# stm32g071_pcb.net
KiCad netlist of a schematic drawn in EAGLE
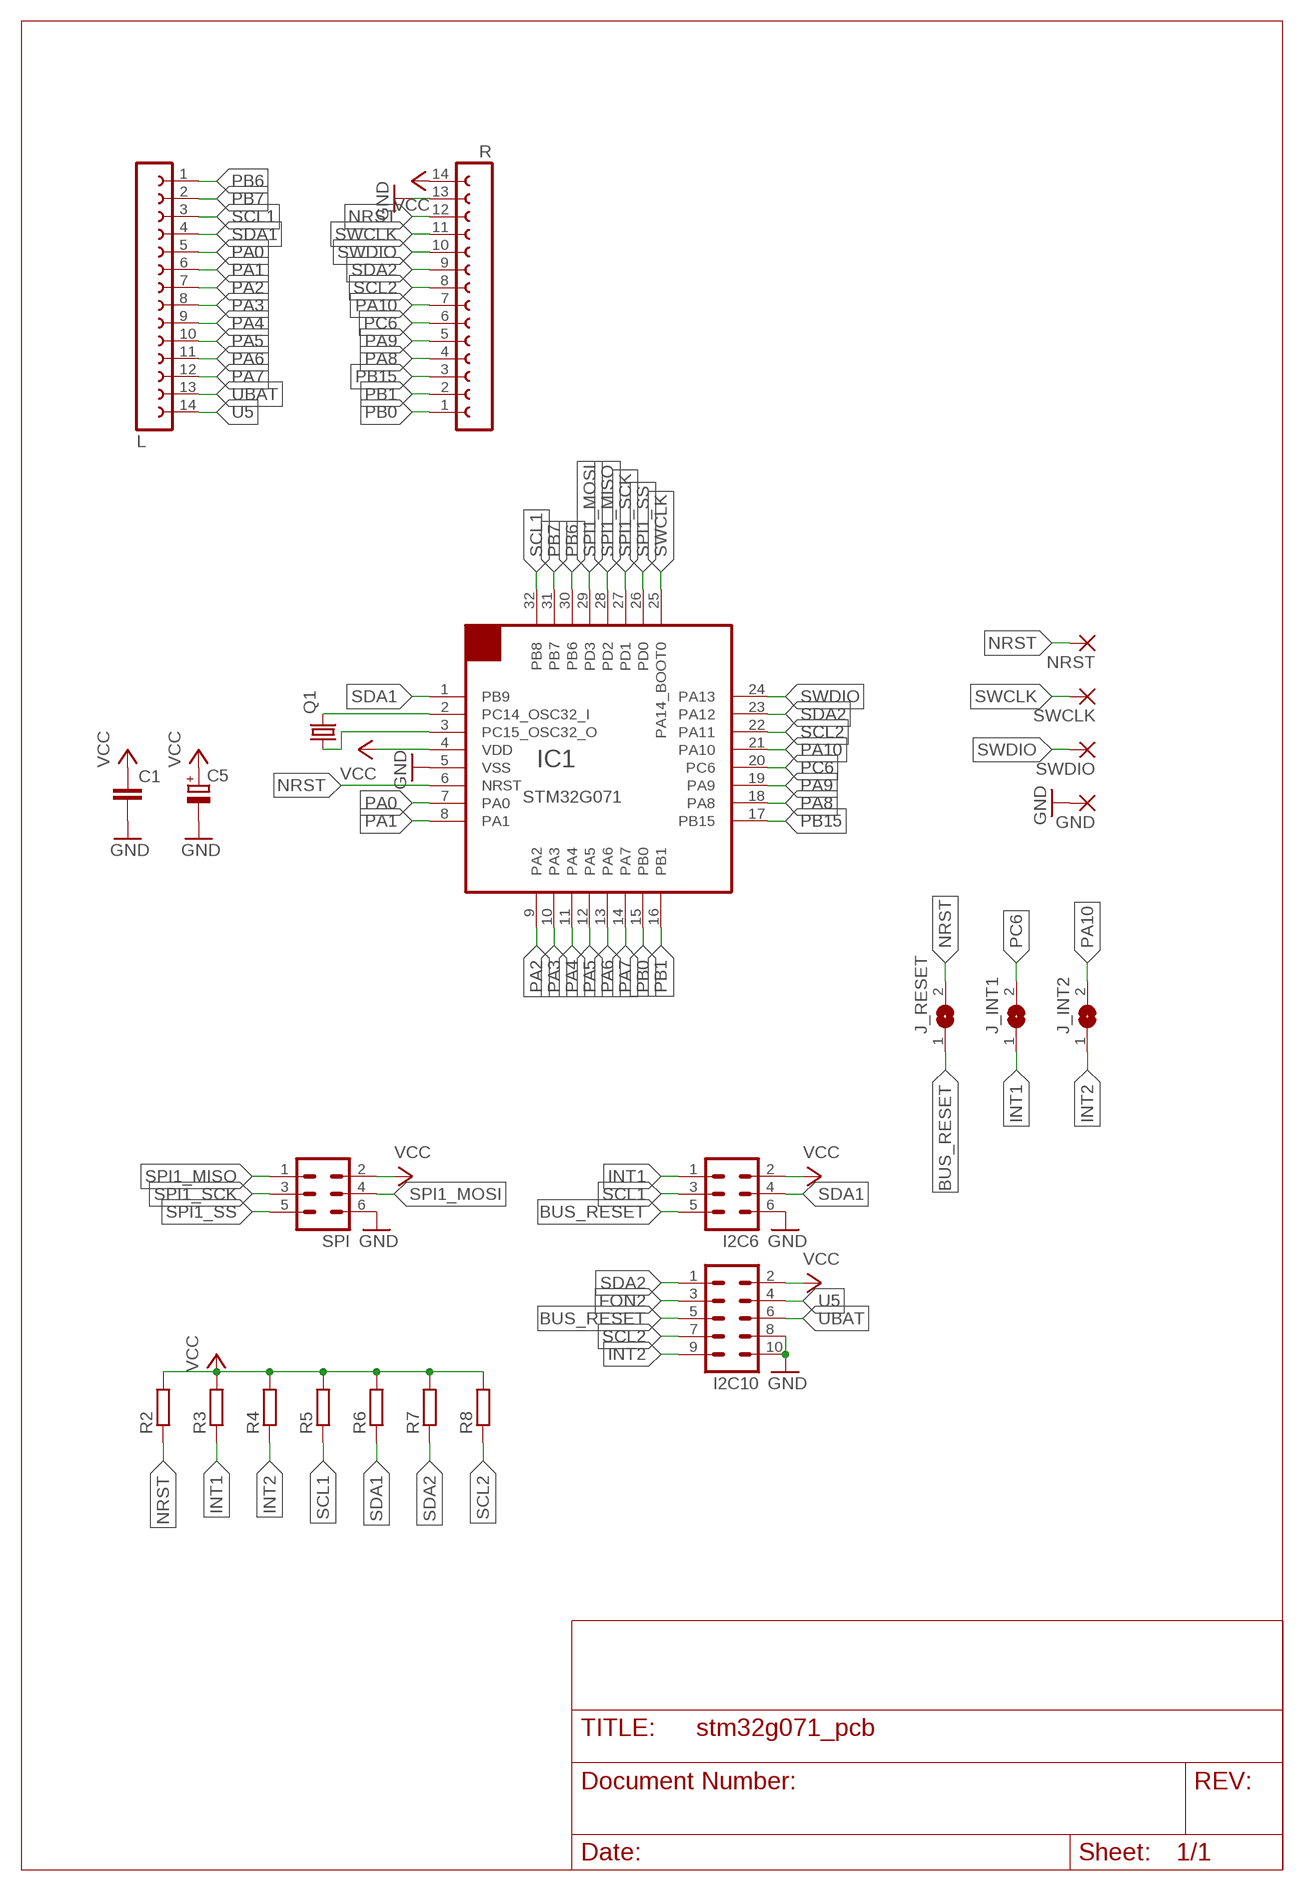
[diagram p0: schematic, sheet 1]

(export (version "E")
  (design (tool "Eeschema 10.0.6"))
  (components
    (comp (ref "C1")
      (value "C-EUC0805")
      (footprint "eagle-import:C0805")
      (libsource (lib "eagle-import") (part "C-EUC0805"))
    )
    (comp (ref "C5")
      (value "CPOL-EUB/3528-21W")
      (footprint "eagle-import:B_3528-21W")
      (libsource (lib "eagle-import") (part "CPOL-EUB/3528-21W"))
    )
    (comp (ref "GND")
      (value "1,6/0,8")
      (footprint "eagle-import:1,6_0,8")
      (libsource (lib "eagle-import") (part "1,6/0,8"))
    )
    (comp (ref "I2C6")
      (value "ML6")
      (footprint "eagle-import:ML6")
      (libsource (lib "eagle-import") (part "ML6"))
    )
    (comp (ref "I2C10")
      (value "ML10")
      (footprint "eagle-import:ML10")
      (libsource (lib "eagle-import") (part "ML10"))
    )
    (comp (ref "IC1")
      (value "STM32G071")
      (footprint "eagle-import:LQFP-32")
      (libsource (lib "eagle-import") (part "STM32G071KBT6N"))
    )
    (comp (ref "J_INT1")
      (value "SJ")
      (footprint "eagle-import:SJ")
      (libsource (lib "eagle-import") (part "SJ"))
    )
    (comp (ref "J_INT2")
      (value "SJ")
      (footprint "eagle-import:SJ")
      (libsource (lib "eagle-import") (part "SJ"))
    )
    (comp (ref "J_RESET")
      (value "SJ")
      (footprint "eagle-import:SJ")
      (libsource (lib "eagle-import") (part "SJ"))
    )
    (comp (ref "L")
      (value "FE14-1")
      (footprint "eagle-import:FE14")
      (libsource (lib "eagle-import") (part "FE14-1"))
    )
    (comp (ref "NRST")
      (value "1,6/0,8")
      (footprint "eagle-import:1,6_0,8")
      (libsource (lib "eagle-import") (part "1,6/0,8"))
    )
    (comp (ref "Q1")
      (value "CRYSTALTC26V")
      (footprint "eagle-import:TC26V")
      (libsource (lib "eagle-import") (part "CRYSTALTC26V"))
    )
    (comp (ref "R")
      (value "FE14-1")
      (footprint "eagle-import:FE14")
      (libsource (lib "eagle-import") (part "FE14-1"))
    )
    (comp (ref "R2")
      (value "R-EU_R0805")
      (footprint "eagle-import:R0805")
      (libsource (lib "eagle-import") (part "R-EU_R0805"))
    )
    (comp (ref "R3")
      (value "R-EU_R0805")
      (footprint "eagle-import:R0805")
      (libsource (lib "eagle-import") (part "R-EU_R0805"))
    )
    (comp (ref "R4")
      (value "R-EU_R0805")
      (footprint "eagle-import:R0805")
      (libsource (lib "eagle-import") (part "R-EU_R0805"))
    )
    (comp (ref "R5")
      (value "R-EU_R0805")
      (footprint "eagle-import:R0805")
      (libsource (lib "eagle-import") (part "R-EU_R0805"))
    )
    (comp (ref "R6")
      (value "R-EU_R0805")
      (footprint "eagle-import:R0805")
      (libsource (lib "eagle-import") (part "R-EU_R0805"))
    )
    (comp (ref "R7")
      (value "R-EU_R0805")
      (footprint "eagle-import:R0805")
      (libsource (lib "eagle-import") (part "R-EU_R0805"))
    )
    (comp (ref "R8")
      (value "R-EU_R0805")
      (footprint "eagle-import:R0805")
      (libsource (lib "eagle-import") (part "R-EU_R0805"))
    )
    (comp (ref "SPI")
      (value "ML6")
      (footprint "eagle-import:ML6")
      (libsource (lib "eagle-import") (part "ML6"))
    )
    (comp (ref "SWCLK")
      (value "1,6/0,8")
      (footprint "eagle-import:1,6_0,8")
      (libsource (lib "eagle-import") (part "1,6/0,8"))
    )
    (comp (ref "SWDIO")
      (value "1,6/0,8")
      (footprint "eagle-import:1,6_0,8")
      (libsource (lib "eagle-import") (part "1,6/0,8"))
    )
  )
  (nets
    (net (code "1") (name "BUS_RESET") (class "Default")
      (node (ref "I2C10") (pin "5") (pinfunction "5_5") (pintype "passive"))
      (node (ref "I2C6") (pin "5") (pinfunction "5_5") (pintype "passive"))
      (node (ref "J_RESET") (pin "1") (pinfunction "1_1") (pintype "passive"))
    )
    (net (code "2") (name "FON2") (class "Default")
      (node (ref "I2C10") (pin "3") (pinfunction "3_3") (pintype "passive"))
    )
    (net (code "3") (name "GND") (class "Default")
      (node (ref "C1") (pin "2") (pinfunction "2_2") (pintype "passive"))
      (node (ref "C5") (pin "-") (pinfunction "-_-") (pintype "passive"))
      (node (ref "GND") (pin "1") (pinfunction "P_1") (pintype "passive"))
      (node (ref "I2C10") (pin "10") (pinfunction "10_10") (pintype "passive"))
      (node (ref "I2C10") (pin "8") (pinfunction "8_8") (pintype "passive"))
      (node (ref "I2C6") (pin "6") (pinfunction "6_6") (pintype "passive"))
      (node (ref "IC1") (pin "5") (pinfunction "VSS_5") (pintype "power_in"))
      (node (ref "R") (pin "13") (pinfunction "13_13") (pintype "passive"))
      (node (ref "SPI") (pin "6") (pinfunction "6_6") (pintype "passive"))
    )
    (net (code "4") (name "INT1") (class "Default")
      (node (ref "I2C6") (pin "1") (pinfunction "1_1") (pintype "passive"))
      (node (ref "J_INT1") (pin "1") (pinfunction "1_1") (pintype "passive"))
      (node (ref "R3") (pin "1") (pinfunction "1_1") (pintype "passive"))
    )
    (net (code "5") (name "INT2") (class "Default")
      (node (ref "I2C10") (pin "9") (pinfunction "9_9") (pintype "passive"))
      (node (ref "J_INT2") (pin "1") (pinfunction "1_1") (pintype "passive"))
      (node (ref "R4") (pin "1") (pinfunction "1_1") (pintype "passive"))
    )
    (net (code "6") (name "NRST") (class "Default")
      (node (ref "IC1") (pin "6") (pinfunction "NRST_6") (pintype "bidirectional"))
      (node (ref "J_RESET") (pin "2") (pinfunction "2_2") (pintype "passive"))
      (node (ref "NRST") (pin "1") (pinfunction "P_1") (pintype "passive"))
      (node (ref "R") (pin "12") (pinfunction "12_12") (pintype "passive"))
      (node (ref "R2") (pin "1") (pinfunction "1_1") (pintype "passive"))
    )
    (net (code "7") (name "Net-(IC1-PC14_OSC32_I)") (class "Default")
      (node (ref "IC1") (pin "2") (pinfunction "PC14_OSC32_I_2") (pintype "bidirectional"))
      (node (ref "Q1") (pin "2") (pinfunction "2_2") (pintype "passive"))
    )
    (net (code "8") (name "Net-(IC1-PC15_OSC32_O)") (class "Default")
      (node (ref "IC1") (pin "3") (pinfunction "PC15_OSC32_O_3") (pintype "bidirectional"))
      (node (ref "Q1") (pin "1") (pinfunction "1_1") (pintype "passive"))
    )
    (net (code "9") (name "PA0") (class "Default")
      (node (ref "IC1") (pin "7") (pinfunction "PA0_7") (pintype "bidirectional"))
      (node (ref "L") (pin "5") (pinfunction "5_5") (pintype "passive"))
    )
    (net (code "10") (name "PA1") (class "Default")
      (node (ref "IC1") (pin "8") (pinfunction "PA1_8") (pintype "bidirectional"))
      (node (ref "L") (pin "6") (pinfunction "6_6") (pintype "passive"))
    )
    (net (code "11") (name "PA2") (class "Default")
      (node (ref "IC1") (pin "9") (pinfunction "PA2_9") (pintype "bidirectional"))
      (node (ref "L") (pin "7") (pinfunction "7_7") (pintype "passive"))
    )
    (net (code "12") (name "PA3") (class "Default")
      (node (ref "IC1") (pin "10") (pinfunction "PA3_10") (pintype "bidirectional"))
      (node (ref "L") (pin "8") (pinfunction "8_8") (pintype "passive"))
    )
    (net (code "13") (name "PA4") (class "Default")
      (node (ref "IC1") (pin "11") (pinfunction "PA4_11") (pintype "bidirectional"))
      (node (ref "L") (pin "9") (pinfunction "9_9") (pintype "passive"))
    )
    (net (code "14") (name "PA5") (class "Default")
      (node (ref "IC1") (pin "12") (pinfunction "PA5_12") (pintype "bidirectional"))
      (node (ref "L") (pin "10") (pinfunction "10_10") (pintype "passive"))
    )
    (net (code "15") (name "PA6") (class "Default")
      (node (ref "IC1") (pin "13") (pinfunction "PA6_13") (pintype "bidirectional"))
      (node (ref "L") (pin "11") (pinfunction "11_11") (pintype "passive"))
    )
    (net (code "16") (name "PA7") (class "Default")
      (node (ref "IC1") (pin "14") (pinfunction "PA7_14") (pintype "bidirectional"))
      (node (ref "L") (pin "12") (pinfunction "12_12") (pintype "passive"))
    )
    (net (code "17") (name "PA8") (class "Default")
      (node (ref "IC1") (pin "18") (pinfunction "PA8_18") (pintype "bidirectional"))
      (node (ref "R") (pin "4") (pinfunction "4_4") (pintype "passive"))
    )
    (net (code "18") (name "PA9") (class "Default")
      (node (ref "IC1") (pin "19") (pinfunction "PA9_19") (pintype "bidirectional"))
      (node (ref "R") (pin "5") (pinfunction "5_5") (pintype "passive"))
    )
    (net (code "19") (name "PA10") (class "Default")
      (node (ref "IC1") (pin "21") (pinfunction "PA10_21") (pintype "bidirectional"))
      (node (ref "J_INT2") (pin "2") (pinfunction "2_2") (pintype "passive"))
      (node (ref "R") (pin "7") (pinfunction "7_7") (pintype "passive"))
    )
    (net (code "20") (name "PB0") (class "Default")
      (node (ref "IC1") (pin "15") (pinfunction "PB0_15") (pintype "bidirectional"))
      (node (ref "R") (pin "1") (pinfunction "1_1") (pintype "passive"))
    )
    (net (code "21") (name "PB1") (class "Default")
      (node (ref "IC1") (pin "16") (pinfunction "PB1_16") (pintype "bidirectional"))
      (node (ref "R") (pin "2") (pinfunction "2_2") (pintype "passive"))
    )
    (net (code "22") (name "PB6") (class "Default")
      (node (ref "IC1") (pin "30") (pinfunction "PB6_30") (pintype "bidirectional"))
      (node (ref "L") (pin "1") (pinfunction "1_1") (pintype "passive"))
    )
    (net (code "23") (name "PB7") (class "Default")
      (node (ref "IC1") (pin "31") (pinfunction "PB7_31") (pintype "bidirectional"))
      (node (ref "L") (pin "2") (pinfunction "2_2") (pintype "passive"))
    )
    (net (code "24") (name "PB15") (class "Default")
      (node (ref "IC1") (pin "17") (pinfunction "PB15_17") (pintype "bidirectional"))
      (node (ref "R") (pin "3") (pinfunction "3_3") (pintype "passive"))
    )
    (net (code "25") (name "PC6") (class "Default")
      (node (ref "IC1") (pin "20") (pinfunction "PC6_20") (pintype "bidirectional"))
      (node (ref "J_INT1") (pin "2") (pinfunction "2_2") (pintype "passive"))
      (node (ref "R") (pin "6") (pinfunction "6_6") (pintype "passive"))
    )
    (net (code "26") (name "SCL1") (class "Default")
      (node (ref "I2C6") (pin "3") (pinfunction "3_3") (pintype "passive"))
      (node (ref "IC1") (pin "32") (pinfunction "PB8_32") (pintype "bidirectional"))
      (node (ref "L") (pin "3") (pinfunction "3_3") (pintype "passive"))
      (node (ref "R5") (pin "1") (pinfunction "1_1") (pintype "passive"))
    )
    (net (code "27") (name "SCL2") (class "Default")
      (node (ref "I2C10") (pin "7") (pinfunction "7_7") (pintype "passive"))
      (node (ref "IC1") (pin "22") (pinfunction "PA11_22") (pintype "bidirectional"))
      (node (ref "R") (pin "8") (pinfunction "8_8") (pintype "passive"))
      (node (ref "R8") (pin "1") (pinfunction "1_1") (pintype "passive"))
    )
    (net (code "28") (name "SDA1") (class "Default")
      (node (ref "I2C6") (pin "4") (pinfunction "4_4") (pintype "passive"))
      (node (ref "IC1") (pin "1") (pinfunction "PB9_1") (pintype "bidirectional"))
      (node (ref "L") (pin "4") (pinfunction "4_4") (pintype "passive"))
      (node (ref "R6") (pin "1") (pinfunction "1_1") (pintype "passive"))
    )
    (net (code "29") (name "SDA2") (class "Default")
      (node (ref "I2C10") (pin "1") (pinfunction "1_1") (pintype "passive"))
      (node (ref "IC1") (pin "23") (pinfunction "PA12_23") (pintype "bidirectional"))
      (node (ref "R") (pin "9") (pinfunction "9_9") (pintype "passive"))
      (node (ref "R7") (pin "1") (pinfunction "1_1") (pintype "passive"))
    )
    (net (code "30") (name "SPI1_MISO") (class "Default")
      (node (ref "IC1") (pin "28") (pinfunction "PD2_28") (pintype "bidirectional"))
      (node (ref "SPI") (pin "1") (pinfunction "1_1") (pintype "passive"))
    )
    (net (code "31") (name "SPI1_MOSI") (class "Default")
      (node (ref "IC1") (pin "29") (pinfunction "PD3_29") (pintype "bidirectional"))
      (node (ref "SPI") (pin "4") (pinfunction "4_4") (pintype "passive"))
    )
    (net (code "32") (name "SPI1_SCK") (class "Default")
      (node (ref "IC1") (pin "27") (pinfunction "PD1_27") (pintype "bidirectional"))
      (node (ref "SPI") (pin "3") (pinfunction "3_3") (pintype "passive"))
    )
    (net (code "33") (name "SPI1_SS") (class "Default")
      (node (ref "IC1") (pin "26") (pinfunction "PD0_26") (pintype "bidirectional"))
      (node (ref "SPI") (pin "5") (pinfunction "5_5") (pintype "passive"))
    )
    (net (code "34") (name "SWCLK") (class "Default")
      (node (ref "IC1") (pin "25") (pinfunction "PA14_BOOT0_25") (pintype "bidirectional"))
      (node (ref "R") (pin "11") (pinfunction "11_11") (pintype "passive"))
      (node (ref "SWCLK") (pin "1") (pinfunction "P_1") (pintype "passive"))
    )
    (net (code "35") (name "SWDIO") (class "Default")
      (node (ref "IC1") (pin "24") (pinfunction "PA13_24") (pintype "bidirectional"))
      (node (ref "R") (pin "10") (pinfunction "10_10") (pintype "passive"))
      (node (ref "SWDIO") (pin "1") (pinfunction "P_1") (pintype "passive"))
    )
    (net (code "36") (name "U5") (class "Default")
      (node (ref "I2C10") (pin "4") (pinfunction "4_4") (pintype "passive"))
      (node (ref "L") (pin "14") (pinfunction "14_14") (pintype "passive"))
    )
    (net (code "37") (name "UBAT") (class "Default")
      (node (ref "I2C10") (pin "6") (pinfunction "6_6") (pintype "passive"))
      (node (ref "L") (pin "13") (pinfunction "13_13") (pintype "passive"))
    )
    (net (code "38") (name "VCC") (class "Default")
      (node (ref "C1") (pin "1") (pinfunction "1_1") (pintype "passive"))
      (node (ref "C5") (pin "+") (pinfunction "+_+") (pintype "passive"))
      (node (ref "I2C10") (pin "2") (pinfunction "2_2") (pintype "passive"))
      (node (ref "I2C6") (pin "2") (pinfunction "2_2") (pintype "passive"))
      (node (ref "IC1") (pin "4") (pinfunction "VDD_4") (pintype "power_in"))
      (node (ref "R") (pin "14") (pinfunction "14_14") (pintype "passive"))
      (node (ref "R2") (pin "2") (pinfunction "2_2") (pintype "passive"))
      (node (ref "R3") (pin "2") (pinfunction "2_2") (pintype "passive"))
      (node (ref "R4") (pin "2") (pinfunction "2_2") (pintype "passive"))
      (node (ref "R5") (pin "2") (pinfunction "2_2") (pintype "passive"))
      (node (ref "R6") (pin "2") (pinfunction "2_2") (pintype "passive"))
      (node (ref "R7") (pin "2") (pinfunction "2_2") (pintype "passive"))
      (node (ref "R8") (pin "2") (pinfunction "2_2") (pintype "passive"))
      (node (ref "SPI") (pin "2") (pinfunction "2_2") (pintype "passive"))
    )
  )
)
